# hall_sensor100a.net
KiCad netlist of a schematic drawn in EAGLE
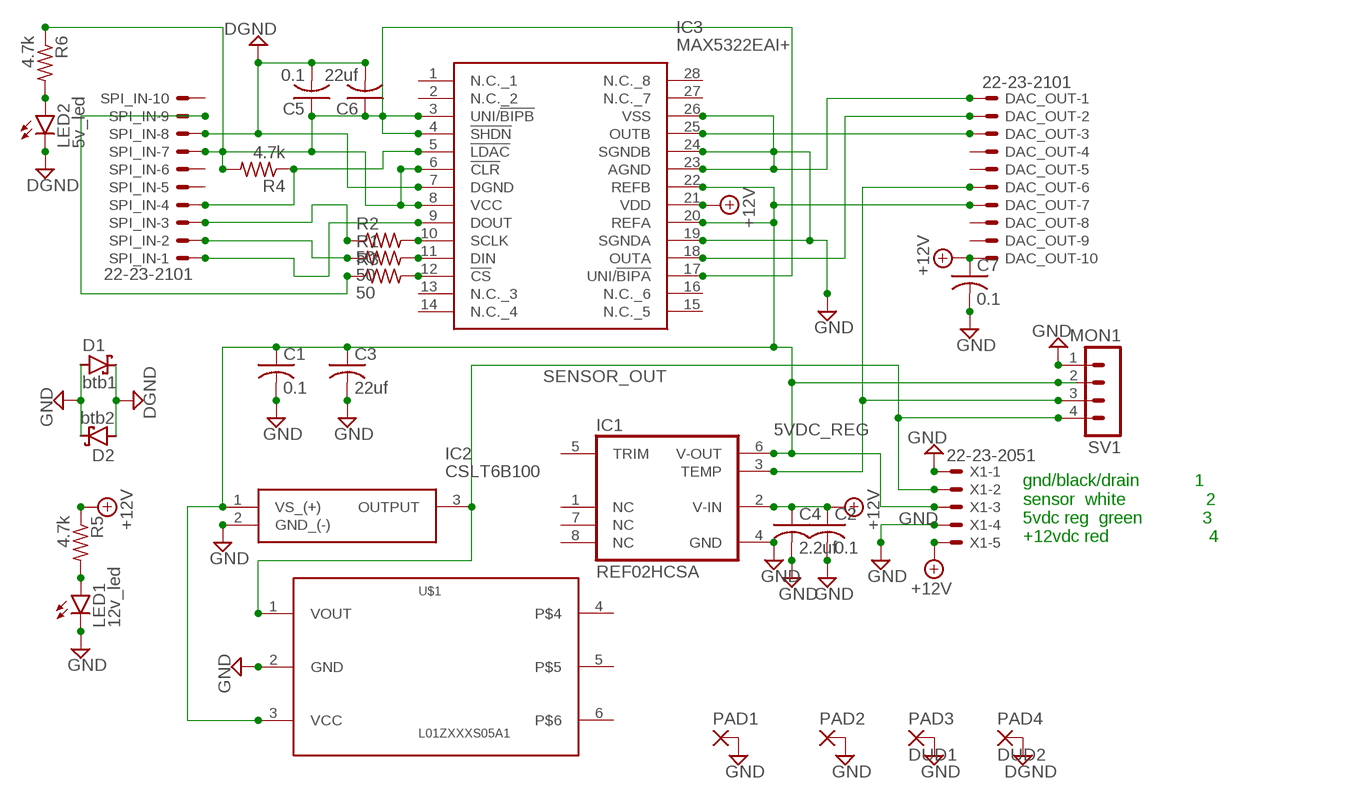
[diagram p0: schematic, sheet 1]

(export (version "E")
  (design (tool "Eeschema 10.0.6"))
  (components
    (comp (ref "C1")
      (value "0.1")
      (footprint "eagle-import:C0805")
      (libsource (lib "eagle-import") (part "C-USC0805"))
    )
    (comp (ref "C2")
      (value "0.1")
      (footprint "eagle-import:C0805")
      (libsource (lib "eagle-import") (part "C-USC0805"))
    )
    (comp (ref "C3")
      (value "22uf")
      (footprint "eagle-import:C0805")
      (libsource (lib "eagle-import") (part "C-USC0805"))
    )
    (comp (ref "C4")
      (value "2.2uf")
      (footprint "eagle-import:C0805")
      (libsource (lib "eagle-import") (part "C-USC0805"))
    )
    (comp (ref "C5")
      (value "0.1")
      (footprint "eagle-import:C0805")
      (libsource (lib "eagle-import") (part "C-USC0805"))
    )
    (comp (ref "C6")
      (value "22uf")
      (footprint "eagle-import:C0805")
      (libsource (lib "eagle-import") (part "C-USC0805"))
    )
    (comp (ref "C7")
      (value "0.1")
      (footprint "eagle-import:C0805")
      (libsource (lib "eagle-import") (part "C-USC0805"))
    )
    (comp (ref "D1")
      (value "btb1")
      (footprint "eagle-import:DO35-7")
      (libsource (lib "eagle-import") (part "SCHOTTKY-DIODEDO35-7"))
    )
    (comp (ref "D2")
      (value "btb2")
      (footprint "eagle-import:DO35-7")
      (libsource (lib "eagle-import") (part "SCHOTTKY-DIODEDO35-7"))
    )
    (comp (ref "DAC_OUT")
      (value "22-23-2101")
      (footprint "eagle-import:22-23-2101")
      (fields (field (name "MF") "MOLEX"))
      (libsource (lib "eagle-import") (part "22-23-2101"))
    )
    (comp (ref "IC1")
      (value "REF02HCSA")
      (footprint "eagle-import:SO08")
      (libsource (lib "eagle-import") (part "REF02HCSA"))
    )
    (comp (ref "IC2")
      (value "CSLT6B100")
      (footprint "eagle-import:CSLT6B100")
      (fields (field (name "MOUSER_PART_NUMBER") "785-CSLT6B100"))
      (libsource (lib "eagle-import") (part "CSLT6B100"))
    )
    (comp (ref "IC3")
      (value "MAX5322EAI+")
      (footprint "eagle-import:SOP65P778X199-28N")
      (fields (field (name "MOUSER_PART_NUMBER") "700-MAX5322EAI") (field (name "RS_PART_NUMBER") "7997645P"))
      (libsource (lib "eagle-import") (part "MAX5322EAI+"))
    )
    (comp (ref "LED1")
      (value "12v_led")
      (footprint "eagle-import:CHIPLED_1206")
      (libsource (lib "eagle-import") (part "LEDCHIPLED_1206"))
    )
    (comp (ref "LED2")
      (value "5v_led")
      (footprint "eagle-import:CHIPLED_1206")
      (libsource (lib "eagle-import") (part "LEDCHIPLED_1206"))
    )
    (comp (ref "PAD1")
      (value "2,15/1,0")
      (footprint "eagle-import:2,15_1,0")
      (libsource (lib "eagle-import") (part "2,15/1,0"))
    )
    (comp (ref "PAD2")
      (value "2,15/1,0")
      (footprint "eagle-import:2,15_1,0")
      (libsource (lib "eagle-import") (part "2,15/1,0"))
    )
    (comp (ref "PAD3")
      (value "DUD1")
      (footprint "eagle-import:2,15_1,0")
      (libsource (lib "eagle-import") (part "2,15/1,0"))
    )
    (comp (ref "PAD4")
      (value "DUD2")
      (footprint "eagle-import:2,15_1,0")
      (libsource (lib "eagle-import") (part "2,15/1,0"))
    )
    (comp (ref "R1")
      (value "50")
      (footprint "eagle-import:M0805")
      (libsource (lib "eagle-import") (part "R-US_M0805"))
    )
    (comp (ref "R2")
      (value "50")
      (footprint "eagle-import:M0805")
      (libsource (lib "eagle-import") (part "R-US_M0805"))
    )
    (comp (ref "R3")
      (value "50")
      (footprint "eagle-import:M0805")
      (libsource (lib "eagle-import") (part "R-US_M0805"))
    )
    (comp (ref "R4")
      (value "4.7k")
      (footprint "eagle-import:M0805")
      (libsource (lib "eagle-import") (part "R-US_M0805"))
    )
    (comp (ref "R5")
      (value "4.7k")
      (footprint "eagle-import:M0805")
      (libsource (lib "eagle-import") (part "R-US_M0805"))
    )
    (comp (ref "R6")
      (value "4.7k")
      (footprint "eagle-import:M0805")
      (libsource (lib "eagle-import") (part "R-US_M0805"))
    )
    (comp (ref "SPI_IN")
      (value "22-23-2101")
      (footprint "eagle-import:22-23-2101")
      (fields (field (name "MF") "MOLEX"))
      (libsource (lib "eagle-import") (part "22-23-2101"))
    )
    (comp (ref "SV1")
      (value "MON1")
      (footprint "eagle-import:MA04-1")
      (libsource (lib "eagle-import") (part "MA04-1"))
    )
    (comp (ref "U$1")
      (value "L01ZXXXS05A1")
      (footprint "eagle-import:DIP2540W53P254L2900H508Q6B")
      (libsource (lib "eagle-import") (part "L01ZXXXS05A1"))
    )
    (comp (ref "X1")
      (value "22-23-2051")
      (footprint "eagle-import:22-23-2051")
      (fields (field (name "MF") "MOLEX"))
      (libsource (lib "eagle-import") (part "22-23-2051"))
    )
  )
  (nets
    (net (code "1") (name "+12V") (class "Default")
      (node (ref "C2") (pin "1") (pinfunction "1_1") (pintype "passive"))
      (node (ref "C4") (pin "1") (pinfunction "1_1") (pintype "passive"))
      (node (ref "C7") (pin "1") (pinfunction "1_1") (pintype "passive"))
      (node (ref "DAC_OUT") (pin "10") (pinfunction "S_10") (pintype "passive"))
      (node (ref "IC1") (pin "2") (pinfunction "V-IN_2") (pintype "power_in"))
      (node (ref "IC3") (pin "21") (pinfunction "VDD_21") (pintype "bidirectional"))
      (node (ref "R5") (pin "1") (pinfunction "1_1") (pintype "passive"))
      (node (ref "X1") (pin "5") (pinfunction "S_5") (pintype "passive"))
    )
    (net (code "2") (name "/5VDC_REG") (class "Default")
      (node (ref "C1") (pin "1") (pinfunction "1_1") (pintype "passive"))
      (node (ref "C3") (pin "1") (pinfunction "1_1") (pintype "passive"))
      (node (ref "DAC_OUT") (pin "7") (pinfunction "S_7") (pintype "passive"))
      (node (ref "IC1") (pin "6") (pinfunction "V-OUT_6") (pintype "output"))
      (node (ref "IC2") (pin "1") (pinfunction "VS_(+)_1") (pintype "bidirectional"))
      (node (ref "IC3") (pin "20") (pinfunction "REFA_20") (pintype "bidirectional"))
      (node (ref "IC3") (pin "22") (pinfunction "REFB_22") (pintype "bidirectional"))
      (node (ref "SV1") (pin "2") (pinfunction "2_2") (pintype "passive"))
      (node (ref "U$1") (pin "3") (pinfunction "VCC_3") (pintype "power_in"))
      (node (ref "X1") (pin "3") (pinfunction "S_3") (pintype "passive"))
    )
    (net (code "3") (name "/SENSOR_OUT") (class "Default")
      (node (ref "IC2") (pin "3") (pinfunction "OUTPUT_3") (pintype "bidirectional"))
      (node (ref "SV1") (pin "4") (pinfunction "4_4") (pintype "passive"))
      (node (ref "U$1") (pin "1") (pinfunction "VOUT_1") (pintype "output"))
      (node (ref "X1") (pin "2") (pinfunction "S_2") (pintype "passive"))
    )
    (net (code "4") (name "DGND") (class "Default")
      (node (ref "C5") (pin "2") (pinfunction "2_2") (pintype "passive"))
      (node (ref "C6") (pin "2") (pinfunction "2_2") (pintype "passive"))
      (node (ref "D1") (pin "C") (pinfunction "C_C") (pintype "passive"))
      (node (ref "D2") (pin "A") (pinfunction "A_A") (pintype "passive"))
      (node (ref "IC3") (pin "7") (pinfunction "DGND_7") (pintype "bidirectional"))
      (node (ref "LED2") (pin "C") (pinfunction "C_C") (pintype "passive"))
      (node (ref "PAD4") (pin "1") (pinfunction "P_1") (pintype "passive"))
      (node (ref "SPI_IN") (pin "8") (pinfunction "S_8") (pintype "passive"))
    )
    (net (code "5") (name "GND") (class "Default")
      (node (ref "C1") (pin "2") (pinfunction "2_2") (pintype "passive"))
      (node (ref "C2") (pin "2") (pinfunction "2_2") (pintype "passive"))
      (node (ref "C3") (pin "2") (pinfunction "2_2") (pintype "passive"))
      (node (ref "C4") (pin "2") (pinfunction "2_2") (pintype "passive"))
      (node (ref "C7") (pin "2") (pinfunction "2_2") (pintype "passive"))
      (node (ref "D1") (pin "A") (pinfunction "A_A") (pintype "passive"))
      (node (ref "D2") (pin "C") (pinfunction "C_C") (pintype "passive"))
      (node (ref "DAC_OUT") (pin "1") (pinfunction "S_1") (pintype "passive"))
      (node (ref "IC1") (pin "4") (pinfunction "GND_4") (pintype "power_in"))
      (node (ref "IC2") (pin "2") (pinfunction "GND_(-)_2") (pintype "bidirectional"))
      (node (ref "IC3") (pin "19") (pinfunction "SGNDA_19") (pintype "bidirectional"))
      (node (ref "IC3") (pin "23") (pinfunction "AGND_23") (pintype "bidirectional"))
      (node (ref "IC3") (pin "24") (pinfunction "SGNDB_24") (pintype "bidirectional"))
      (node (ref "IC3") (pin "26") (pinfunction "VSS_26") (pintype "bidirectional"))
      (node (ref "LED1") (pin "C") (pinfunction "C_C") (pintype "passive"))
      (node (ref "PAD1") (pin "1") (pinfunction "P_1") (pintype "passive"))
      (node (ref "PAD2") (pin "1") (pinfunction "P_1") (pintype "passive"))
      (node (ref "PAD3") (pin "1") (pinfunction "P_1") (pintype "passive"))
      (node (ref "SV1") (pin "1") (pinfunction "1_1") (pintype "passive"))
      (node (ref "U$1") (pin "2") (pinfunction "GND_2") (pintype "power_in"))
      (node (ref "X1") (pin "1") (pinfunction "S_1") (pintype "passive"))
      (node (ref "X1") (pin "4") (pinfunction "S_4") (pintype "passive"))
    )
    (net (code "6") (name "Net-(DAC_OUTC-S)") (class "Default")
      (node (ref "DAC_OUT") (pin "2") (pinfunction "S_2") (pintype "passive"))
      (node (ref "IC3") (pin "18") (pinfunction "OUTA_18") (pintype "bidirectional"))
    )
    (net (code "7") (name "Net-(DAC_OUTD-S)") (class "Default")
      (node (ref "DAC_OUT") (pin "3") (pinfunction "S_3") (pintype "passive"))
      (node (ref "IC3") (pin "25") (pinfunction "OUTB_25") (pintype "bidirectional"))
    )
    (net (code "8") (name "Net-(DAC_OUTG-S)") (class "Default")
      (node (ref "DAC_OUT") (pin "6") (pinfunction "S_6") (pintype "passive"))
      (node (ref "IC1") (pin "3") (pinfunction "TEMP_3") (pintype "output"))
      (node (ref "SV1") (pin "3") (pinfunction "3_3") (pintype "passive"))
    )
    (net (code "9") (name "Net-(IC3-DIN)") (class "Default")
      (node (ref "IC3") (pin "11") (pinfunction "DIN_11") (pintype "bidirectional"))
      (node (ref "R1") (pin "2") (pinfunction "2_2") (pintype "passive"))
    )
    (net (code "10") (name "Net-(IC3-DOUT)") (class "Default")
      (node (ref "IC3") (pin "9") (pinfunction "DOUT_9") (pintype "bidirectional"))
      (node (ref "SPI_IN") (pin "1") (pinfunction "S_1") (pintype "passive"))
    )
    (net (code "11") (name "Net-(IC3-SCLK)") (class "Default")
      (node (ref "IC3") (pin "10") (pinfunction "SCLK_10") (pintype "bidirectional"))
      (node (ref "R2") (pin "2") (pinfunction "2_2") (pintype "passive"))
    )
    (net (code "12") (name "Net-(IC3-UNI{slash}~{BIPA})") (class "Default")
      (node (ref "C5") (pin "1") (pinfunction "1_1") (pintype "passive"))
      (node (ref "C6") (pin "1") (pinfunction "1_1") (pintype "passive"))
      (node (ref "IC3") (pin "17") (pinfunction "UNI/~{BIPA}_17") (pintype "bidirectional"))
      (node (ref "IC3") (pin "3") (pinfunction "UNI/~{BIPB}_3") (pintype "bidirectional"))
      (node (ref "IC3") (pin "4") (pinfunction "~{SHDN}_4") (pintype "bidirectional"))
      (node (ref "IC3") (pin "6") (pinfunction "~{CLR}_6") (pintype "bidirectional"))
      (node (ref "IC3") (pin "8") (pinfunction "VCC_8") (pintype "bidirectional"))
      (node (ref "R4") (pin "2") (pinfunction "2_2") (pintype "passive"))
      (node (ref "R6") (pin "1") (pinfunction "1_1") (pintype "passive"))
      (node (ref "SPI_IN") (pin "7") (pinfunction "S_7") (pintype "passive"))
    )
    (net (code "13") (name "Net-(IC3-~{CS})") (class "Default")
      (node (ref "IC3") (pin "12") (pinfunction "~{CS}_12") (pintype "bidirectional"))
      (node (ref "R3") (pin "2") (pinfunction "2_2") (pintype "passive"))
    )
    (net (code "14") (name "Net-(IC3-~{LDAC})") (class "Default")
      (node (ref "IC3") (pin "5") (pinfunction "~{LDAC}_5") (pintype "bidirectional"))
      (node (ref "R4") (pin "1") (pinfunction "1_1") (pintype "passive"))
      (node (ref "SPI_IN") (pin "4") (pinfunction "S_4") (pintype "passive"))
    )
    (net (code "15") (name "Net-(LED1-PadA)") (class "Default")
      (node (ref "LED1") (pin "A") (pinfunction "A_A") (pintype "passive"))
      (node (ref "R5") (pin "2") (pinfunction "2_2") (pintype "passive"))
    )
    (net (code "16") (name "Net-(LED2-PadA)") (class "Default")
      (node (ref "LED2") (pin "A") (pinfunction "A_A") (pintype "passive"))
      (node (ref "R6") (pin "2") (pinfunction "2_2") (pintype "passive"))
    )
    (net (code "17") (name "Net-(SPI_INC-S)") (class "Default")
      (node (ref "R1") (pin "1") (pinfunction "1_1") (pintype "passive"))
      (node (ref "SPI_IN") (pin "2") (pinfunction "S_2") (pintype "passive"))
    )
    (net (code "18") (name "Net-(SPI_IND-S)") (class "Default")
      (node (ref "R2") (pin "1") (pinfunction "1_1") (pintype "passive"))
      (node (ref "SPI_IN") (pin "3") (pinfunction "S_3") (pintype "passive"))
    )
    (net (code "19") (name "Net-(SPI_INJ-S)") (class "Default")
      (node (ref "R3") (pin "1") (pinfunction "1_1") (pintype "passive"))
      (node (ref "SPI_IN") (pin "9") (pinfunction "S_9") (pintype "passive"))
    )
    (net (code "20") (name "unconnected-(DAC_OUTE-S-Pad4)") (class "Default")
      (node (ref "DAC_OUT") (pin "4") (pinfunction "S_4") (pintype "passive"))
    )
    (net (code "21") (name "unconnected-(DAC_OUTF-S-Pad5)") (class "Default")
      (node (ref "DAC_OUT") (pin "5") (pinfunction "S_5") (pintype "passive"))
    )
    (net (code "22") (name "unconnected-(DAC_OUTI-S-Pad8)") (class "Default")
      (node (ref "DAC_OUT") (pin "8") (pinfunction "S_8") (pintype "passive"))
    )
    (net (code "23") (name "unconnected-(DAC_OUTJ-S-Pad9)") (class "Default")
      (node (ref "DAC_OUT") (pin "9") (pinfunction "S_9") (pintype "passive"))
    )
    (net (code "24") (name "unconnected-(IC1-NC-Pad1)") (class "Default")
      (node (ref "IC1") (pin "1") (pinfunction "NC_1") (pintype "no_connect"))
    )
    (net (code "25") (name "unconnected-(IC1-NC-Pad7)") (class "Default")
      (node (ref "IC1") (pin "7") (pinfunction "NC_7") (pintype "no_connect"))
    )
    (net (code "26") (name "unconnected-(IC1-NC-Pad8)") (class "Default")
      (node (ref "IC1") (pin "8") (pinfunction "NC_8") (pintype "no_connect"))
    )
    (net (code "27") (name "unconnected-(IC1-TRIM-Pad5)") (class "Default")
      (node (ref "IC1") (pin "5") (pinfunction "TRIM_5") (pintype "input"))
    )
    (net (code "28") (name "unconnected-(IC3-N.C._1-Pad1)") (class "Default")
      (node (ref "IC3") (pin "1") (pinfunction "N.C._1_1") (pintype "bidirectional"))
    )
    (net (code "29") (name "unconnected-(IC3-N.C._2-Pad2)") (class "Default")
      (node (ref "IC3") (pin "2") (pinfunction "N.C._2_2") (pintype "bidirectional"))
    )
    (net (code "30") (name "unconnected-(IC3-N.C._3-Pad13)") (class "Default")
      (node (ref "IC3") (pin "13") (pinfunction "N.C._3_13") (pintype "bidirectional"))
    )
    (net (code "31") (name "unconnected-(IC3-N.C._4-Pad14)") (class "Default")
      (node (ref "IC3") (pin "14") (pinfunction "N.C._4_14") (pintype "bidirectional"))
    )
    (net (code "32") (name "unconnected-(IC3-N.C._5-Pad15)") (class "Default")
      (node (ref "IC3") (pin "15") (pinfunction "N.C._5_15") (pintype "bidirectional"))
    )
    (net (code "33") (name "unconnected-(IC3-N.C._6-Pad16)") (class "Default")
      (node (ref "IC3") (pin "16") (pinfunction "N.C._6_16") (pintype "bidirectional"))
    )
    (net (code "34") (name "unconnected-(IC3-N.C._7-Pad27)") (class "Default")
      (node (ref "IC3") (pin "27") (pinfunction "N.C._7_27") (pintype "bidirectional"))
    )
    (net (code "35") (name "unconnected-(IC3-N.C._8-Pad28)") (class "Default")
      (node (ref "IC3") (pin "28") (pinfunction "N.C._8_28") (pintype "bidirectional"))
    )
    (net (code "36") (name "unconnected-(SPI_INB-S-Pad10)") (class "Default")
      (node (ref "SPI_IN") (pin "10") (pinfunction "S_10") (pintype "passive"))
    )
    (net (code "37") (name "unconnected-(SPI_INF-S-Pad5)") (class "Default")
      (node (ref "SPI_IN") (pin "5") (pinfunction "S_5") (pintype "passive"))
    )
    (net (code "38") (name "unconnected-(SPI_ING-S-Pad6)") (class "Default")
      (node (ref "SPI_IN") (pin "6") (pinfunction "S_6") (pintype "passive"))
    )
    (net (code "39") (name "unconnected-(U$1-P$4-Pad4)") (class "Default")
      (node (ref "U$1") (pin "4") (pinfunction "P$4_4") (pintype "no_connect"))
    )
    (net (code "40") (name "unconnected-(U$1-P$5-Pad5)") (class "Default")
      (node (ref "U$1") (pin "5") (pinfunction "P$5_5") (pintype "no_connect"))
    )
    (net (code "41") (name "unconnected-(U$1-P$6-Pad6)") (class "Default")
      (node (ref "U$1") (pin "6") (pinfunction "P$6_6") (pintype "no_connect"))
    )
  )
)
